# photoduino_shield_v_3_0.net
KiCad netlist of a schematic drawn in EAGLE
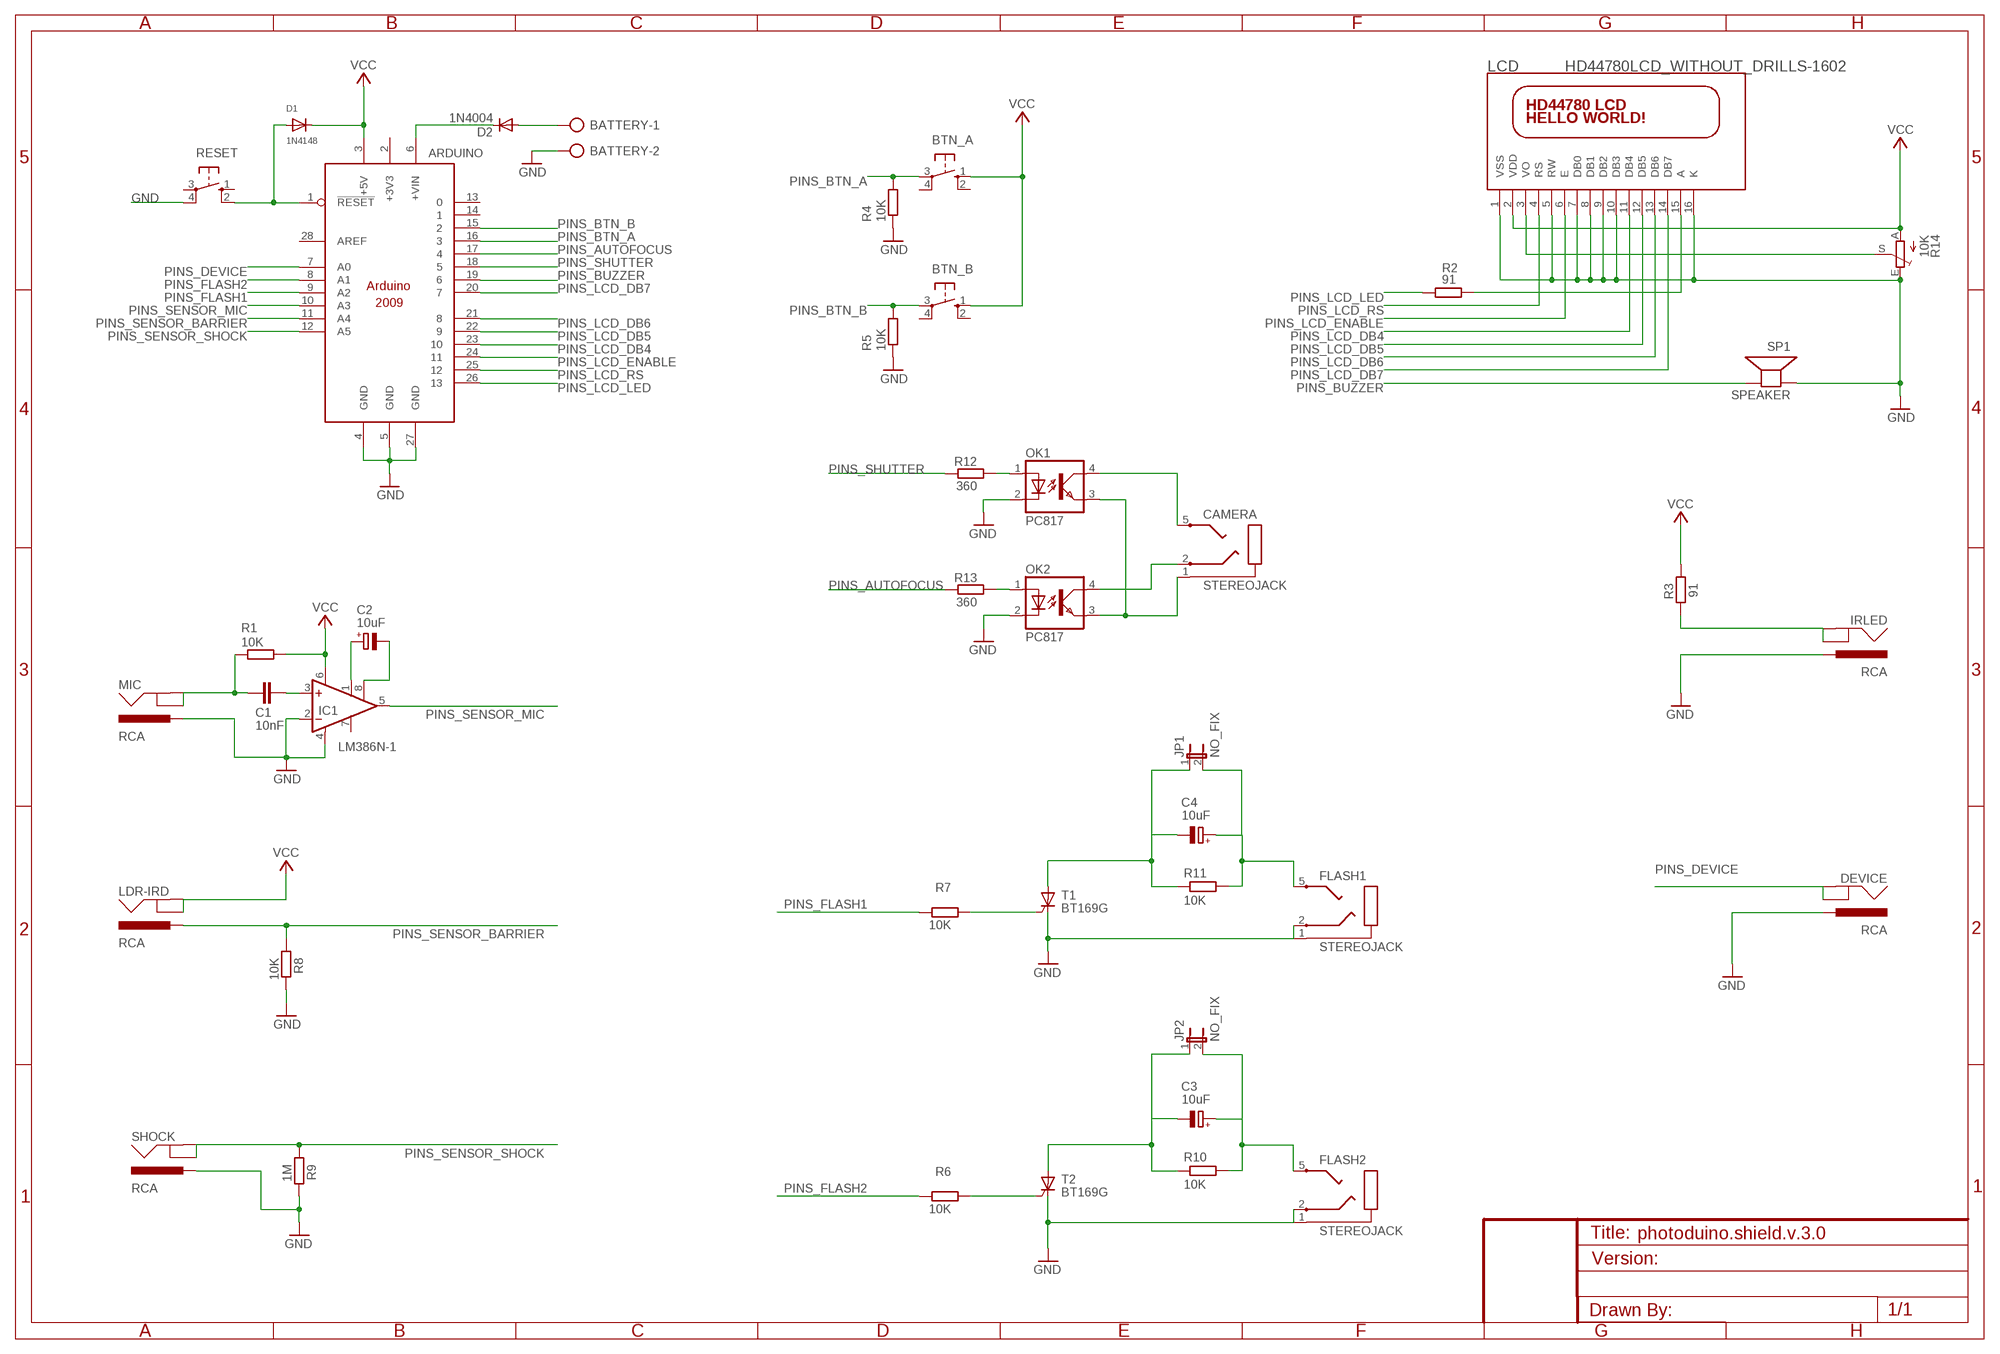
[diagram p0: schematic, sheet 1]

(export (version "E")
  (design (tool "Eeschema 10.0.6"))
  (components
    (comp (ref "ARDUINO")
      (value "ARDUINO2009_12")
      (footprint "eagle-import:ARDUINO2009_2")
      (libsource (lib "eagle-import") (part "ARDUINO2009_12"))
    )
    (comp (ref "BATTERY")
      (value "AK500/2")
      (footprint "eagle-import:AK500_2")
      (libsource (lib "eagle-import") (part "AK500/2"))
    )
    (comp (ref "BTN_A")
      (value "10-XX")
      (footprint "eagle-import:B3F-10XX")
      (fields (field (name "MPN") "B3F-1000"))
      (libsource (lib "eagle-import") (part "10-XX"))
    )
    (comp (ref "BTN_B")
      (value "10-XX")
      (footprint "eagle-import:B3F-10XX")
      (fields (field (name "MPN") "B3F-1000"))
      (libsource (lib "eagle-import") (part "10-XX"))
    )
    (comp (ref "C1")
      (value "10nF")
      (footprint "eagle-import:C050-025X075")
      (libsource (lib "eagle-import") (part "C-EU050-025X075"))
    )
    (comp (ref "C2")
      (value "10uF")
      (footprint "eagle-import:E2,5-7")
      (libsource (lib "eagle-import") (part "CPOL-EUE2.5-7"))
    )
    (comp (ref "C3")
      (value "10uF")
      (footprint "eagle-import:E2,5-7")
      (libsource (lib "eagle-import") (part "CPOL-EUE2.5-7"))
    )
    (comp (ref "C4")
      (value "10uF")
      (footprint "eagle-import:E2,5-7")
      (libsource (lib "eagle-import") (part "CPOL-EUE2.5-7"))
    )
    (comp (ref "CAMERA")
      (value "STEREOJACK")
      (footprint "eagle-import:STX3100-3N")
      (libsource (lib "eagle-import") (part "STEREOJACK"))
    )
    (comp (ref "D1")
      (value "1N4148")
      (footprint "eagle-import:DO-1N4148")
      (libsource (lib "eagle-import") (part "DIODEDO-1N4148"))
    )
    (comp (ref "D2")
      (value "1N4004")
      (footprint "eagle-import:DO41-10")
      (libsource (lib "eagle-import") (part "1N4004"))
    )
    (comp (ref "DEVICE")
      (value "RCA")
      (footprint "eagle-import:RCA_4UCON")
      (libsource (lib "eagle-import") (part "RCA_JACK_4UCON"))
    )
    (comp (ref "FLASH1")
      (value "STEREOJACK")
      (footprint "eagle-import:STX3100-3N")
      (libsource (lib "eagle-import") (part "STEREOJACK"))
    )
    (comp (ref "FLASH2")
      (value "STEREOJACK")
      (footprint "eagle-import:STX3100-3N")
      (libsource (lib "eagle-import") (part "STEREOJACK"))
    )
    (comp (ref "IC1")
      (value "LM386N-1")
      (footprint "eagle-import:DIL08")
      (libsource (lib "eagle-import") (part "LM386?-N1"))
    )
    (comp (ref "IRLED")
      (value "RCA")
      (footprint "eagle-import:RCA_4UCON")
      (libsource (lib "eagle-import") (part "RCA_JACK_4UCON"))
    )
    (comp (ref "JP1")
      (value "NO_FIX")
      (footprint "eagle-import:JP1")
      (libsource (lib "eagle-import") (part "JP1E"))
    )
    (comp (ref "JP2")
      (value "NO_FIX")
      (footprint "eagle-import:JP1")
      (libsource (lib "eagle-import") (part "JP1E"))
    )
    (comp (ref "LCD")
      (value "HD44780LCD_WITHOUT_DRILLS-1602")
      (footprint "eagle-import:LCD1602")
      (libsource (lib "eagle-import") (part "HD44780LCD_WITHOUT_DRILLS-1602"))
    )
    (comp (ref "LDR-IRD")
      (value "RCA")
      (footprint "eagle-import:RCA_4UCON")
      (libsource (lib "eagle-import") (part "RCA_JACK_4UCON"))
    )
    (comp (ref "MIC")
      (value "RCA")
      (footprint "eagle-import:RCA_4UCON")
      (libsource (lib "eagle-import") (part "RCA_JACK_4UCON"))
    )
    (comp (ref "OK1")
      (value "PC817")
      (footprint "eagle-import:DIL04")
      (fields (field (name "MPN") "PC817X4J000F"))
      (libsource (lib "eagle-import") (part "PC817"))
    )
    (comp (ref "OK2")
      (value "PC817")
      (footprint "eagle-import:DIL04")
      (fields (field (name "MPN") "PC817X4J000F"))
      (libsource (lib "eagle-import") (part "PC817"))
    )
    (comp (ref "R1")
      (value "10K")
      (footprint "eagle-import:0207_7")
      (libsource (lib "eagle-import") (part "R-EU_0207/7"))
    )
    (comp (ref "R2")
      (value "91")
      (footprint "eagle-import:0207_7")
      (libsource (lib "eagle-import") (part "R-EU_0207/7"))
    )
    (comp (ref "R3")
      (value "91")
      (footprint "eagle-import:0207_7")
      (libsource (lib "eagle-import") (part "R-EU_0207/7"))
    )
    (comp (ref "R4")
      (value "10K")
      (footprint "eagle-import:0207_7")
      (libsource (lib "eagle-import") (part "R-EU_0207/7"))
    )
    (comp (ref "R5")
      (value "10K")
      (footprint "eagle-import:0207_7")
      (libsource (lib "eagle-import") (part "R-EU_0207/7"))
    )
    (comp (ref "R6")
      (value "10K")
      (footprint "eagle-import:0207_7")
      (libsource (lib "eagle-import") (part "R-EU_0207/7"))
    )
    (comp (ref "R7")
      (value "10K")
      (footprint "eagle-import:0207_7")
      (libsource (lib "eagle-import") (part "R-EU_0207/7"))
    )
    (comp (ref "R8")
      (value "10K")
      (footprint "eagle-import:0207_7")
      (libsource (lib "eagle-import") (part "R-EU_0207/7"))
    )
    (comp (ref "R9")
      (value "1M")
      (footprint "eagle-import:0207_7")
      (libsource (lib "eagle-import") (part "R-EU_0207/7"))
    )
    (comp (ref "R10")
      (value "10K")
      (footprint "eagle-import:0207_7")
      (libsource (lib "eagle-import") (part "R-EU_0207/7"))
    )
    (comp (ref "R11")
      (value "10K")
      (footprint "eagle-import:0207_7")
      (libsource (lib "eagle-import") (part "R-EU_0207/7"))
    )
    (comp (ref "R12")
      (value "360")
      (footprint "eagle-import:0207_7")
      (libsource (lib "eagle-import") (part "R-EU_0207/7"))
    )
    (comp (ref "R13")
      (value "360")
      (footprint "eagle-import:0207_7")
      (libsource (lib "eagle-import") (part "R-EU_0207/7"))
    )
    (comp (ref "R14")
      (value "10K")
      (footprint "eagle-import:B25U")
      (libsource (lib "eagle-import") (part "TRIM_EU-B25U"))
    )
    (comp (ref "RESET")
      (value "10-XX")
      (footprint "eagle-import:B3F-10XX")
      (fields (field (name "MPN") "B3F-1000"))
      (libsource (lib "eagle-import") (part "10-XX"))
    )
    (comp (ref "SHOCK")
      (value "RCA")
      (footprint "eagle-import:RCA_4UCON")
      (libsource (lib "eagle-import") (part "RCA_JACK_4UCON"))
    )
    (comp (ref "SP1")
      (value "SPEAKER")
      (footprint "eagle-import:PS12")
      (libsource (lib "eagle-import") (part "SPEAKER/PS12"))
    )
    (comp (ref "T1")
      (value "BT169G")
      (footprint "eagle-import:TO92-2")
      (libsource (lib "eagle-import") (part "BT169"))
    )
    (comp (ref "T2")
      (value "BT169G")
      (footprint "eagle-import:TO92-2")
      (libsource (lib "eagle-import") (part "BT169"))
    )
  )
  (nets
    (net (code "1") (name "/+3V3") (class "Default")
      (node (ref "ARDUINO") (pin "2") (pinfunction "+3V3_2") (pintype "power_in"))
    )
    (net (code "2") (name "/PINS_AUTOFOCUS") (class "Default")
      (node (ref "ARDUINO") (pin "17") (pinfunction "4_17") (pintype "bidirectional"))
      (node (ref "R13") (pin "2") (pinfunction "2_2") (pintype "passive"))
    )
    (net (code "3") (name "/PINS_BTN_A") (class "Default")
      (node (ref "ARDUINO") (pin "16") (pinfunction "3_16") (pintype "bidirectional"))
      (node (ref "BTN_A") (pin "3") (pinfunction "P_3") (pintype "passive"))
      (node (ref "R4") (pin "2") (pinfunction "2_2") (pintype "passive"))
    )
    (net (code "4") (name "/PINS_BTN_B") (class "Default")
      (node (ref "ARDUINO") (pin "15") (pinfunction "2_15") (pintype "bidirectional"))
      (node (ref "BTN_B") (pin "3") (pinfunction "P_3") (pintype "passive"))
      (node (ref "R5") (pin "2") (pinfunction "2_2") (pintype "passive"))
    )
    (net (code "5") (name "/PINS_BUZZER") (class "Default")
      (node (ref "ARDUINO") (pin "19") (pinfunction "6_19") (pintype "bidirectional"))
      (node (ref "SP1") (pin "P$2") (pinfunction "-_P$2") (pintype "passive"))
    )
    (net (code "6") (name "/PINS_DEVICE") (class "Default")
      (node (ref "ARDUINO") (pin "7") (pinfunction "A0_7") (pintype "bidirectional"))
      (node (ref "DEVICE") (pin "BREAK") (pinfunction "BREAK_BREAK") (pintype "bidirectional"))
      (node (ref "DEVICE") (pin "SPRING") (pinfunction "SPRING_SPRING") (pintype "bidirectional"))
    )
    (net (code "7") (name "/PINS_FLASH1") (class "Default")
      (node (ref "ARDUINO") (pin "9") (pinfunction "A2_9") (pintype "bidirectional"))
      (node (ref "R7") (pin "2") (pinfunction "2_2") (pintype "passive"))
    )
    (net (code "8") (name "/PINS_FLASH2") (class "Default")
      (node (ref "ARDUINO") (pin "8") (pinfunction "A1_8") (pintype "bidirectional"))
      (node (ref "R6") (pin "2") (pinfunction "2_2") (pintype "passive"))
    )
    (net (code "9") (name "/PINS_LCD_DB4") (class "Default")
      (node (ref "ARDUINO") (pin "23") (pinfunction "10_23") (pintype "bidirectional"))
      (node (ref "LCD") (pin "11") (pinfunction "DB4_11") (pintype "bidirectional"))
    )
    (net (code "10") (name "/PINS_LCD_DB5") (class "Default")
      (node (ref "ARDUINO") (pin "22") (pinfunction "9_22") (pintype "bidirectional"))
      (node (ref "LCD") (pin "12") (pinfunction "DB5_12") (pintype "bidirectional"))
    )
    (net (code "11") (name "/PINS_LCD_DB6") (class "Default")
      (node (ref "ARDUINO") (pin "21") (pinfunction "8_21") (pintype "bidirectional"))
      (node (ref "LCD") (pin "13") (pinfunction "DB6_13") (pintype "bidirectional"))
    )
    (net (code "12") (name "/PINS_LCD_DB7") (class "Default")
      (node (ref "ARDUINO") (pin "20") (pinfunction "7_20") (pintype "bidirectional"))
      (node (ref "LCD") (pin "14") (pinfunction "DB7_14") (pintype "bidirectional"))
    )
    (net (code "13") (name "/PINS_LCD_ENABLE") (class "Default")
      (node (ref "ARDUINO") (pin "24") (pinfunction "11_24") (pintype "bidirectional"))
      (node (ref "LCD") (pin "6") (pinfunction "E_6") (pintype "input"))
    )
    (net (code "14") (name "/PINS_LCD_LED") (class "Default")
      (node (ref "ARDUINO") (pin "26") (pinfunction "13_26") (pintype "bidirectional"))
      (node (ref "R2") (pin "2") (pinfunction "2_2") (pintype "passive"))
    )
    (net (code "15") (name "/PINS_LCD_RS") (class "Default")
      (node (ref "ARDUINO") (pin "25") (pinfunction "12_25") (pintype "bidirectional"))
      (node (ref "LCD") (pin "4") (pinfunction "RS_4") (pintype "input"))
    )
    (net (code "16") (name "/PINS_SENSOR_BARRIER") (class "Default")
      (node (ref "ARDUINO") (pin "11") (pinfunction "A4_11") (pintype "bidirectional"))
      (node (ref "LDR-IRD") (pin "BARREL") (pinfunction "BARREL_BARREL") (pintype "bidirectional"))
      (node (ref "R8") (pin "1") (pinfunction "1_1") (pintype "passive"))
    )
    (net (code "17") (name "/PINS_SENSOR_MIC") (class "Default")
      (node (ref "ARDUINO") (pin "10") (pinfunction "A3_10") (pintype "bidirectional"))
      (node (ref "IC1") (pin "5") (pinfunction "OUT_5") (pintype "output"))
    )
    (net (code "18") (name "/PINS_SENSOR_SHOCK") (class "Default")
      (node (ref "ARDUINO") (pin "12") (pinfunction "A5_12") (pintype "bidirectional"))
      (node (ref "R9") (pin "1") (pinfunction "1_1") (pintype "passive"))
      (node (ref "SHOCK") (pin "BREAK") (pinfunction "BREAK_BREAK") (pintype "bidirectional"))
      (node (ref "SHOCK") (pin "SPRING") (pinfunction "SPRING_SPRING") (pintype "bidirectional"))
    )
    (net (code "19") (name "/PINS_SHUTTER") (class "Default")
      (node (ref "ARDUINO") (pin "18") (pinfunction "5_18") (pintype "bidirectional"))
      (node (ref "R12") (pin "2") (pinfunction "2_2") (pintype "passive"))
    )
    (net (code "20") (name "GND") (class "Default")
      (node (ref "ARDUINO") (pin "27") (pinfunction "GND_27") (pintype "power_in"))
      (node (ref "ARDUINO") (pin "4") (pinfunction "GND_4") (pintype "power_in"))
      (node (ref "ARDUINO") (pin "5") (pinfunction "GND_5") (pintype "power_in"))
      (node (ref "BATTERY") (pin "2") (pinfunction "KL_2") (pintype "passive"))
      (node (ref "DEVICE") (pin "BARREL") (pinfunction "BARREL_BARREL") (pintype "bidirectional"))
      (node (ref "FLASH1") (pin "1") (pinfunction "1_1") (pintype "passive"))
      (node (ref "FLASH1") (pin "2") (pinfunction "2_2") (pintype "passive"))
      (node (ref "FLASH2") (pin "1") (pinfunction "1_1") (pintype "passive"))
      (node (ref "FLASH2") (pin "2") (pinfunction "2_2") (pintype "passive"))
      (node (ref "IC1") (pin "2") (pinfunction "-IN_2") (pintype "input"))
      (node (ref "IC1") (pin "4") (pinfunction "GND_4") (pintype "power_in"))
      (node (ref "IRLED") (pin "BARREL") (pinfunction "BARREL_BARREL") (pintype "bidirectional"))
      (node (ref "LCD") (pin "1") (pinfunction "VSS_1") (pintype "power_in"))
      (node (ref "LCD") (pin "10") (pinfunction "DB3_10") (pintype "bidirectional"))
      (node (ref "LCD") (pin "16") (pinfunction "K_16") (pintype "input"))
      (node (ref "LCD") (pin "5") (pinfunction "RW_5") (pintype "input"))
      (node (ref "LCD") (pin "7") (pinfunction "DB0_7") (pintype "bidirectional"))
      (node (ref "LCD") (pin "8") (pinfunction "DB1_8") (pintype "bidirectional"))
      (node (ref "LCD") (pin "9") (pinfunction "DB2_9") (pintype "bidirectional"))
      (node (ref "MIC") (pin "BARREL") (pinfunction "BARREL_BARREL") (pintype "bidirectional"))
      (node (ref "OK1") (pin "2") (pinfunction "C_2") (pintype "passive"))
      (node (ref "OK2") (pin "2") (pinfunction "C_2") (pintype "passive"))
      (node (ref "R14") (pin "E") (pinfunction "E_E") (pintype "passive"))
      (node (ref "R4") (pin "1") (pinfunction "1_1") (pintype "passive"))
      (node (ref "R5") (pin "1") (pinfunction "1_1") (pintype "passive"))
      (node (ref "R8") (pin "2") (pinfunction "2_2") (pintype "passive"))
      (node (ref "R9") (pin "2") (pinfunction "2_2") (pintype "passive"))
      (node (ref "RESET") (pin "4") (pinfunction "P1_4") (pintype "passive"))
      (node (ref "SHOCK") (pin "BARREL") (pinfunction "BARREL_BARREL") (pintype "bidirectional"))
      (node (ref "SP1") (pin "P$1") (pinfunction "+_P$1") (pintype "passive"))
      (node (ref "T1") (pin "C") (pinfunction "C_C") (pintype "passive"))
      (node (ref "T2") (pin "C") (pinfunction "C_C") (pintype "passive"))
    )
    (net (code "21") (name "Net-(ARDUINO-+VIN)") (class "Default")
      (node (ref "ARDUINO") (pin "6") (pinfunction "+VIN_6") (pintype "bidirectional"))
      (node (ref "D2") (pin "C") (pinfunction "C_C") (pintype "passive"))
    )
    (net (code "22") (name "Net-(ARDUINO-~{RESET})") (class "Default")
      (node (ref "ARDUINO") (pin "1") (pinfunction "~{RESET}_1") (pintype "bidirectional"))
      (node (ref "D1") (pin "A") (pinfunction "A_A") (pintype "passive"))
      (node (ref "RESET") (pin "2") (pinfunction "S1_2") (pintype "passive"))
    )
    (net (code "23") (name "Net-(BATTERYA-KL)") (class "Default")
      (node (ref "BATTERY") (pin "1") (pinfunction "KL_1") (pintype "passive"))
      (node (ref "D2") (pin "A") (pinfunction "A_A") (pintype "passive"))
    )
    (net (code "24") (name "Net-(C1-Pad2)") (class "Default")
      (node (ref "C1") (pin "2") (pinfunction "2_2") (pintype "passive"))
      (node (ref "MIC") (pin "BREAK") (pinfunction "BREAK_BREAK") (pintype "bidirectional"))
      (node (ref "MIC") (pin "SPRING") (pinfunction "SPRING_SPRING") (pintype "bidirectional"))
      (node (ref "R1") (pin "1") (pinfunction "1_1") (pintype "passive"))
    )
    (net (code "25") (name "Net-(C2-Pad+)") (class "Default")
      (node (ref "C2") (pin "+") (pinfunction "+_+") (pintype "passive"))
      (node (ref "IC1") (pin "1") (pinfunction "GAIN_1") (pintype "passive"))
    )
    (net (code "26") (name "Net-(C2-Pad-)") (class "Default")
      (node (ref "C2") (pin "-") (pinfunction "-_-") (pintype "passive"))
      (node (ref "IC1") (pin "8") (pinfunction "GAIN_8") (pintype "passive"))
    )
    (net (code "27") (name "Net-(C3-Pad+)") (class "Default")
      (node (ref "C3") (pin "+") (pinfunction "+_+") (pintype "passive"))
      (node (ref "FLASH2") (pin "5") (pinfunction "5_5") (pintype "passive"))
      (node (ref "JP2") (pin "2") (pinfunction "2_2") (pintype "passive"))
      (node (ref "R10") (pin "2") (pinfunction "2_2") (pintype "passive"))
    )
    (net (code "28") (name "Net-(C3-Pad-)") (class "Default")
      (node (ref "C3") (pin "-") (pinfunction "-_-") (pintype "passive"))
      (node (ref "JP2") (pin "1") (pinfunction "1_1") (pintype "passive"))
      (node (ref "R10") (pin "1") (pinfunction "1_1") (pintype "passive"))
      (node (ref "T2") (pin "A") (pinfunction "A_A") (pintype "passive"))
    )
    (net (code "29") (name "Net-(C4-Pad+)") (class "Default")
      (node (ref "C4") (pin "+") (pinfunction "+_+") (pintype "passive"))
      (node (ref "FLASH1") (pin "5") (pinfunction "5_5") (pintype "passive"))
      (node (ref "JP1") (pin "2") (pinfunction "2_2") (pintype "passive"))
      (node (ref "R11") (pin "2") (pinfunction "2_2") (pintype "passive"))
    )
    (net (code "30") (name "Net-(C4-Pad-)") (class "Default")
      (node (ref "C4") (pin "-") (pinfunction "-_-") (pintype "passive"))
      (node (ref "JP1") (pin "1") (pinfunction "1_1") (pintype "passive"))
      (node (ref "R11") (pin "1") (pinfunction "1_1") (pintype "passive"))
      (node (ref "T1") (pin "A") (pinfunction "A_A") (pintype "passive"))
    )
    (net (code "31") (name "Net-(IC1-+IN)") (class "Default")
      (node (ref "C1") (pin "1") (pinfunction "1_1") (pintype "passive"))
      (node (ref "IC1") (pin "3") (pinfunction "+IN_3") (pintype "input"))
    )
    (net (code "32") (name "Net-(IRLED-PadBREAK)") (class "Default")
      (node (ref "IRLED") (pin "BREAK") (pinfunction "BREAK_BREAK") (pintype "bidirectional"))
      (node (ref "IRLED") (pin "SPRING") (pinfunction "SPRING_SPRING") (pintype "bidirectional"))
      (node (ref "R3") (pin "2") (pinfunction "2_2") (pintype "passive"))
    )
    (net (code "33") (name "Net-(LCD-A)") (class "Default")
      (node (ref "LCD") (pin "15") (pinfunction "A_15") (pintype "input"))
      (node (ref "R2") (pin "1") (pinfunction "1_1") (pintype "passive"))
    )
    (net (code "34") (name "Net-(LCD-VO)") (class "Default")
      (node (ref "LCD") (pin "3") (pinfunction "VO_3") (pintype "input"))
      (node (ref "R14") (pin "S") (pinfunction "S_S") (pintype "passive"))
    )
    (net (code "35") (name "Net-(OK1-A)") (class "Default")
      (node (ref "OK1") (pin "1") (pinfunction "A_1") (pintype "passive"))
      (node (ref "R12") (pin "1") (pinfunction "1_1") (pintype "passive"))
    )
    (net (code "36") (name "Net-(OK1-COL)") (class "Default")
      (node (ref "CAMERA") (pin "5") (pinfunction "5_5") (pintype "passive"))
      (node (ref "OK1") (pin "4") (pinfunction "COL_4") (pintype "passive"))
    )
    (net (code "37") (name "Net-(OK1-EMIT)") (class "Default")
      (node (ref "CAMERA") (pin "1") (pinfunction "1_1") (pintype "passive"))
      (node (ref "OK1") (pin "3") (pinfunction "EMIT_3") (pintype "passive"))
      (node (ref "OK2") (pin "3") (pinfunction "EMIT_3") (pintype "passive"))
    )
    (net (code "38") (name "Net-(OK2-A)") (class "Default")
      (node (ref "OK2") (pin "1") (pinfunction "A_1") (pintype "passive"))
      (node (ref "R13") (pin "1") (pinfunction "1_1") (pintype "passive"))
    )
    (net (code "39") (name "Net-(OK2-COL)") (class "Default")
      (node (ref "CAMERA") (pin "2") (pinfunction "2_2") (pintype "passive"))
      (node (ref "OK2") (pin "4") (pinfunction "COL_4") (pintype "passive"))
    )
    (net (code "40") (name "Net-(R6-Pad1)") (class "Default")
      (node (ref "R6") (pin "1") (pinfunction "1_1") (pintype "passive"))
      (node (ref "T2") (pin "G") (pinfunction "G_G") (pintype "passive"))
    )
    (net (code "41") (name "Net-(R7-Pad1)") (class "Default")
      (node (ref "R7") (pin "1") (pinfunction "1_1") (pintype "passive"))
      (node (ref "T1") (pin "G") (pinfunction "G_G") (pintype "passive"))
    )
    (net (code "42") (name "VCC") (class "Default")
      (node (ref "ARDUINO") (pin "3") (pinfunction "+5V_3") (pintype "power_in"))
      (node (ref "BTN_A") (pin "1") (pinfunction "S_1") (pintype "passive"))
      (node (ref "BTN_B") (pin "1") (pinfunction "S_1") (pintype "passive"))
      (node (ref "D1") (pin "C") (pinfunction "C_C") (pintype "passive"))
      (node (ref "IC1") (pin "6") (pinfunction "VS_6") (pintype "power_in"))
      (node (ref "LCD") (pin "2") (pinfunction "VDD_2") (pintype "power_in"))
      (node (ref "LDR-IRD") (pin "BREAK") (pinfunction "BREAK_BREAK") (pintype "bidirectional"))
      (node (ref "LDR-IRD") (pin "SPRING") (pinfunction "SPRING_SPRING") (pintype "bidirectional"))
      (node (ref "R1") (pin "2") (pinfunction "2_2") (pintype "passive"))
      (node (ref "R14") (pin "A") (pinfunction "A_A") (pintype "passive"))
      (node (ref "R3") (pin "1") (pinfunction "1_1") (pintype "passive"))
    )
    (net (code "43") (name "unconnected-(ARDUINO-0-Pad13)") (class "Default")
      (node (ref "ARDUINO") (pin "13") (pinfunction "0_13") (pintype "bidirectional"))
    )
    (net (code "44") (name "unconnected-(ARDUINO-1-Pad14)") (class "Default")
      (node (ref "ARDUINO") (pin "14") (pinfunction "1_14") (pintype "bidirectional"))
    )
    (net (code "45") (name "unconnected-(ARDUINO-AREF-Pad28)") (class "Default")
      (node (ref "ARDUINO") (pin "28") (pinfunction "AREF_28") (pintype "bidirectional"))
    )
    (net (code "46") (name "unconnected-(BTN_A-P1-Pad4)") (class "Default")
      (node (ref "BTN_A") (pin "4") (pinfunction "P1_4") (pintype "passive"))
    )
    (net (code "47") (name "unconnected-(BTN_A-S1-Pad2)") (class "Default")
      (node (ref "BTN_A") (pin "2") (pinfunction "S1_2") (pintype "passive"))
    )
    (net (code "48") (name "unconnected-(BTN_B-P1-Pad4)") (class "Default")
      (node (ref "BTN_B") (pin "4") (pinfunction "P1_4") (pintype "passive"))
    )
    (net (code "49") (name "unconnected-(BTN_B-S1-Pad2)") (class "Default")
      (node (ref "BTN_B") (pin "2") (pinfunction "S1_2") (pintype "passive"))
    )
    (net (code "50") (name "unconnected-(IC1-BYPASS-Pad7)") (class "Default")
      (node (ref "IC1") (pin "7") (pinfunction "BYPASS_7") (pintype "passive"))
    )
    (net (code "51") (name "unconnected-(RESET-P-Pad3)") (class "Default")
      (node (ref "RESET") (pin "3") (pinfunction "P_3") (pintype "passive"))
    )
    (net (code "52") (name "unconnected-(RESET-S-Pad1)") (class "Default")
      (node (ref "RESET") (pin "1") (pinfunction "S_1") (pintype "passive"))
    )
  )
)
